# HDC2022.net
KiCad netlist of a schematic drawn in Altium Designer
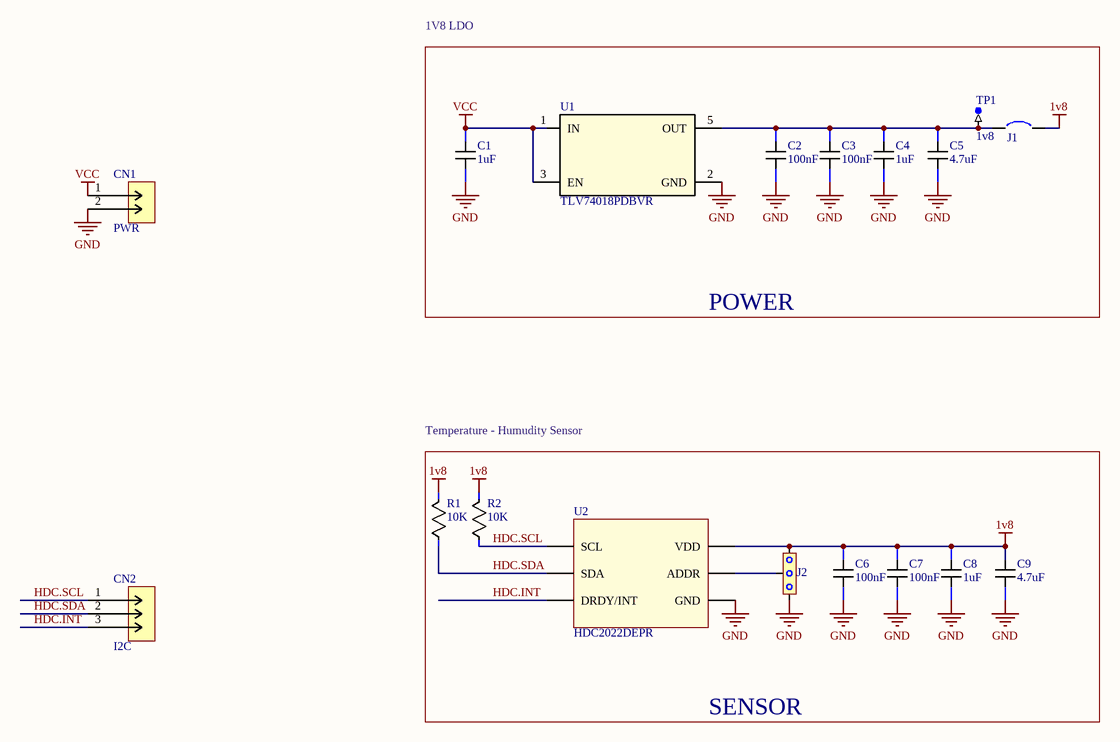
[diagram p0: HDC2022.SchDoc]

(export (version "E")
  (design (tool "Eeschema 10.0.6"))
  (components
    (comp (ref "C1") (value "1uF") (footprint "CAP_0805") (libsource (lib "HDC2022") (part "Capacitor")))
    (comp (ref "C2") (value "100nF") (footprint "CAP_0805") (libsource (lib "HDC2022") (part "Capacitor")))
    (comp (ref "C3") (value "100nF") (footprint "CAP_0805") (libsource (lib "HDC2022") (part "Capacitor")))
    (comp (ref "C4") (value "1uF") (footprint "CAP_0805") (libsource (lib "HDC2022") (part "Capacitor")))
    (comp (ref "C5") (value "4.7uF") (footprint "CAP_0805") (libsource (lib "HDC2022") (part "Capacitor")))
    (comp (ref "C6") (value "100nF") (footprint "CAP_0805") (libsource (lib "HDC2022") (part "Capacitor")))
    (comp (ref "C7") (value "100nF") (footprint "CAP_0805") (libsource (lib "HDC2022") (part "Capacitor")))
    (comp (ref "C8") (value "1uF") (footprint "CAP_0805") (libsource (lib "HDC2022") (part "Capacitor")))
    (comp (ref "C9") (value "4.7uF") (footprint "CAP_0805") (libsource (lib "HDC2022") (part "Capacitor")))
    (comp (ref "CN1")
      (value "PWR")
      (footprint "HD_2pin_2.54mm_male")
      (libsource (lib "HDC2022") (part "HD_2pin_2.54mm_Male"))
    )
    (comp (ref "CN2")
      (value "I2C")
      (footprint "HD_3pin_2.54mm_male")
      (libsource (lib "HDC2022") (part "HD_3pin_2.54mm_Male"))
    )
    (comp (ref "J1")
      (value "Jumper")
      (footprint "SB_0603")
      (fields (field (name "PUBLISHER") "Altium Limited"))
      (libsource (lib "HDC2022") (part "Jumper"))
    )
    (comp (ref "J2")
      (value "JUMPER_3Pin")
      (footprint "SB_0603 - 3 Pin")
      (libsource (lib "HDC2022") (part "JUMPER_3Pin"))
    )
    (comp (ref "R1") (value "10K") (footprint "RES_0805") (libsource (lib "HDC2022") (part "Resistor")))
    (comp (ref "R2") (value "10K") (footprint "RES_0805") (libsource (lib "HDC2022") (part "Resistor")))
    (comp (ref "TP1") (value "1v8") (footprint "TP") (libsource (lib "HDC2022") (part "Test Point")))
    (comp (ref "U1")
      (value "TLV74018PDBVR")
      (footprint "SOIC_DBVR_TEX")
      (fields (field (name "MANUFACTURER") "Texas Instruments"))
      (libsource (lib "HDC2022") (part "TLV74018PDBVR"))
    )
    (comp (ref "U2")
      (value "HDC2022DEPR")
      (footprint "WSON-6")
      (fields (field (name "MANUFACTURER") "Texas Instruments"))
      (libsource (lib "HDC2022") (part "HDC2022DEPR"))
    )
  )
  (nets
    (net (code "1") (name "/HDC.INT") (class "Default")
      (node (ref "CN2") (pin "3") (pinfunction "23_3") (pintype "passive"))
      (node (ref "U2") (pin "4") (pinfunction "DRDY/INT_4") (pintype "passive"))
    )
    (net (code "2") (name "/HDC.SCL") (class "Default")
      (node (ref "CN2") (pin "1") (pinfunction "1_1") (pintype "passive"))
      (node (ref "R2") (pin "1") (pinfunction "1_1") (pintype "passive"))
      (node (ref "U2") (pin "6") (pinfunction "SCL_6") (pintype "passive"))
    )
    (net (code "3") (name "/HDC.SDA") (class "Default")
      (node (ref "CN2") (pin "2") (pinfunction "2_2") (pintype "passive"))
      (node (ref "R1") (pin "1") (pinfunction "1_1") (pintype "passive"))
      (node (ref "U2") (pin "1") (pinfunction "SDA_1") (pintype "passive"))
    )
    (net (code "4") (name "1v8") (class "Default")
      (node (ref "C6") (pin "2") (pinfunction "2_2") (pintype "passive"))
      (node (ref "C7") (pin "2") (pinfunction "2_2") (pintype "passive"))
      (node (ref "C8") (pin "2") (pinfunction "2_2") (pintype "passive"))
      (node (ref "C9") (pin "2") (pinfunction "2_2") (pintype "passive"))
      (node (ref "J1") (pin "2") (pinfunction "2_2") (pintype "passive"))
      (node (ref "J2") (pin "1") (pinfunction "1_1") (pintype "passive"))
      (node (ref "R1") (pin "2") (pinfunction "2_2") (pintype "passive"))
      (node (ref "R2") (pin "2") (pinfunction "2_2") (pintype "passive"))
      (node (ref "U2") (pin "5") (pinfunction "VDD_5") (pintype "passive"))
    )
    (net (code "5") (name "GND") (class "Default")
      (node (ref "C1") (pin "1") (pinfunction "1_1") (pintype "passive"))
      (node (ref "C2") (pin "1") (pinfunction "1_1") (pintype "passive"))
      (node (ref "C3") (pin "1") (pinfunction "1_1") (pintype "passive"))
      (node (ref "C4") (pin "1") (pinfunction "1_1") (pintype "passive"))
      (node (ref "C5") (pin "1") (pinfunction "1_1") (pintype "passive"))
      (node (ref "C6") (pin "1") (pinfunction "1_1") (pintype "passive"))
      (node (ref "C7") (pin "1") (pinfunction "1_1") (pintype "passive"))
      (node (ref "C8") (pin "1") (pinfunction "1_1") (pintype "passive"))
      (node (ref "C9") (pin "1") (pinfunction "1_1") (pintype "passive"))
      (node (ref "CN1") (pin "2") (pinfunction "2_2") (pintype "passive"))
      (node (ref "J2") (pin "3") (pinfunction "3_3") (pintype "passive"))
      (node (ref "U1") (pin "2") (pinfunction "GND_2") (pintype "passive"))
      (node (ref "U2") (pin "2") (pinfunction "GND_2") (pintype "passive"))
    )
    (net (code "6") (name "Net-(U1-OUT)") (class "Default")
      (node (ref "C2") (pin "2") (pinfunction "2_2") (pintype "passive"))
      (node (ref "C3") (pin "2") (pinfunction "2_2") (pintype "passive"))
      (node (ref "C4") (pin "2") (pinfunction "2_2") (pintype "passive"))
      (node (ref "C5") (pin "2") (pinfunction "2_2") (pintype "passive"))
      (node (ref "J1") (pin "1") (pinfunction "1_1") (pintype "passive"))
      (node (ref "TP1") (pin "1") (pinfunction "1_1") (pintype "input"))
      (node (ref "U1") (pin "5") (pinfunction "OUT_5") (pintype "passive"))
    )
    (net (code "7") (name "Net-(U2-ADDR)") (class "Default")
      (node (ref "J2") (pin "2") (pinfunction "2_2") (pintype "passive"))
      (node (ref "U2") (pin "3") (pinfunction "ADDR_3") (pintype "passive"))
    )
    (net (code "8") (name "VCC") (class "Default")
      (node (ref "C1") (pin "2") (pinfunction "2_2") (pintype "passive"))
      (node (ref "CN1") (pin "1") (pinfunction "1_1") (pintype "passive"))
      (node (ref "U1") (pin "1") (pinfunction "IN_1") (pintype "passive"))
      (node (ref "U1") (pin "3") (pinfunction "EN_3") (pintype "passive"))
    )
    (net (code "9") (name "unconnected-(U1-NC-Pad4)") (class "Default")
      (node (ref "U1") (pin "4") (pinfunction "NC_4") (pintype "passive"))
    )
  )
)
